# Kyocera_breakout_board.net
KiCad netlist of a schematic drawn in EasyEDA
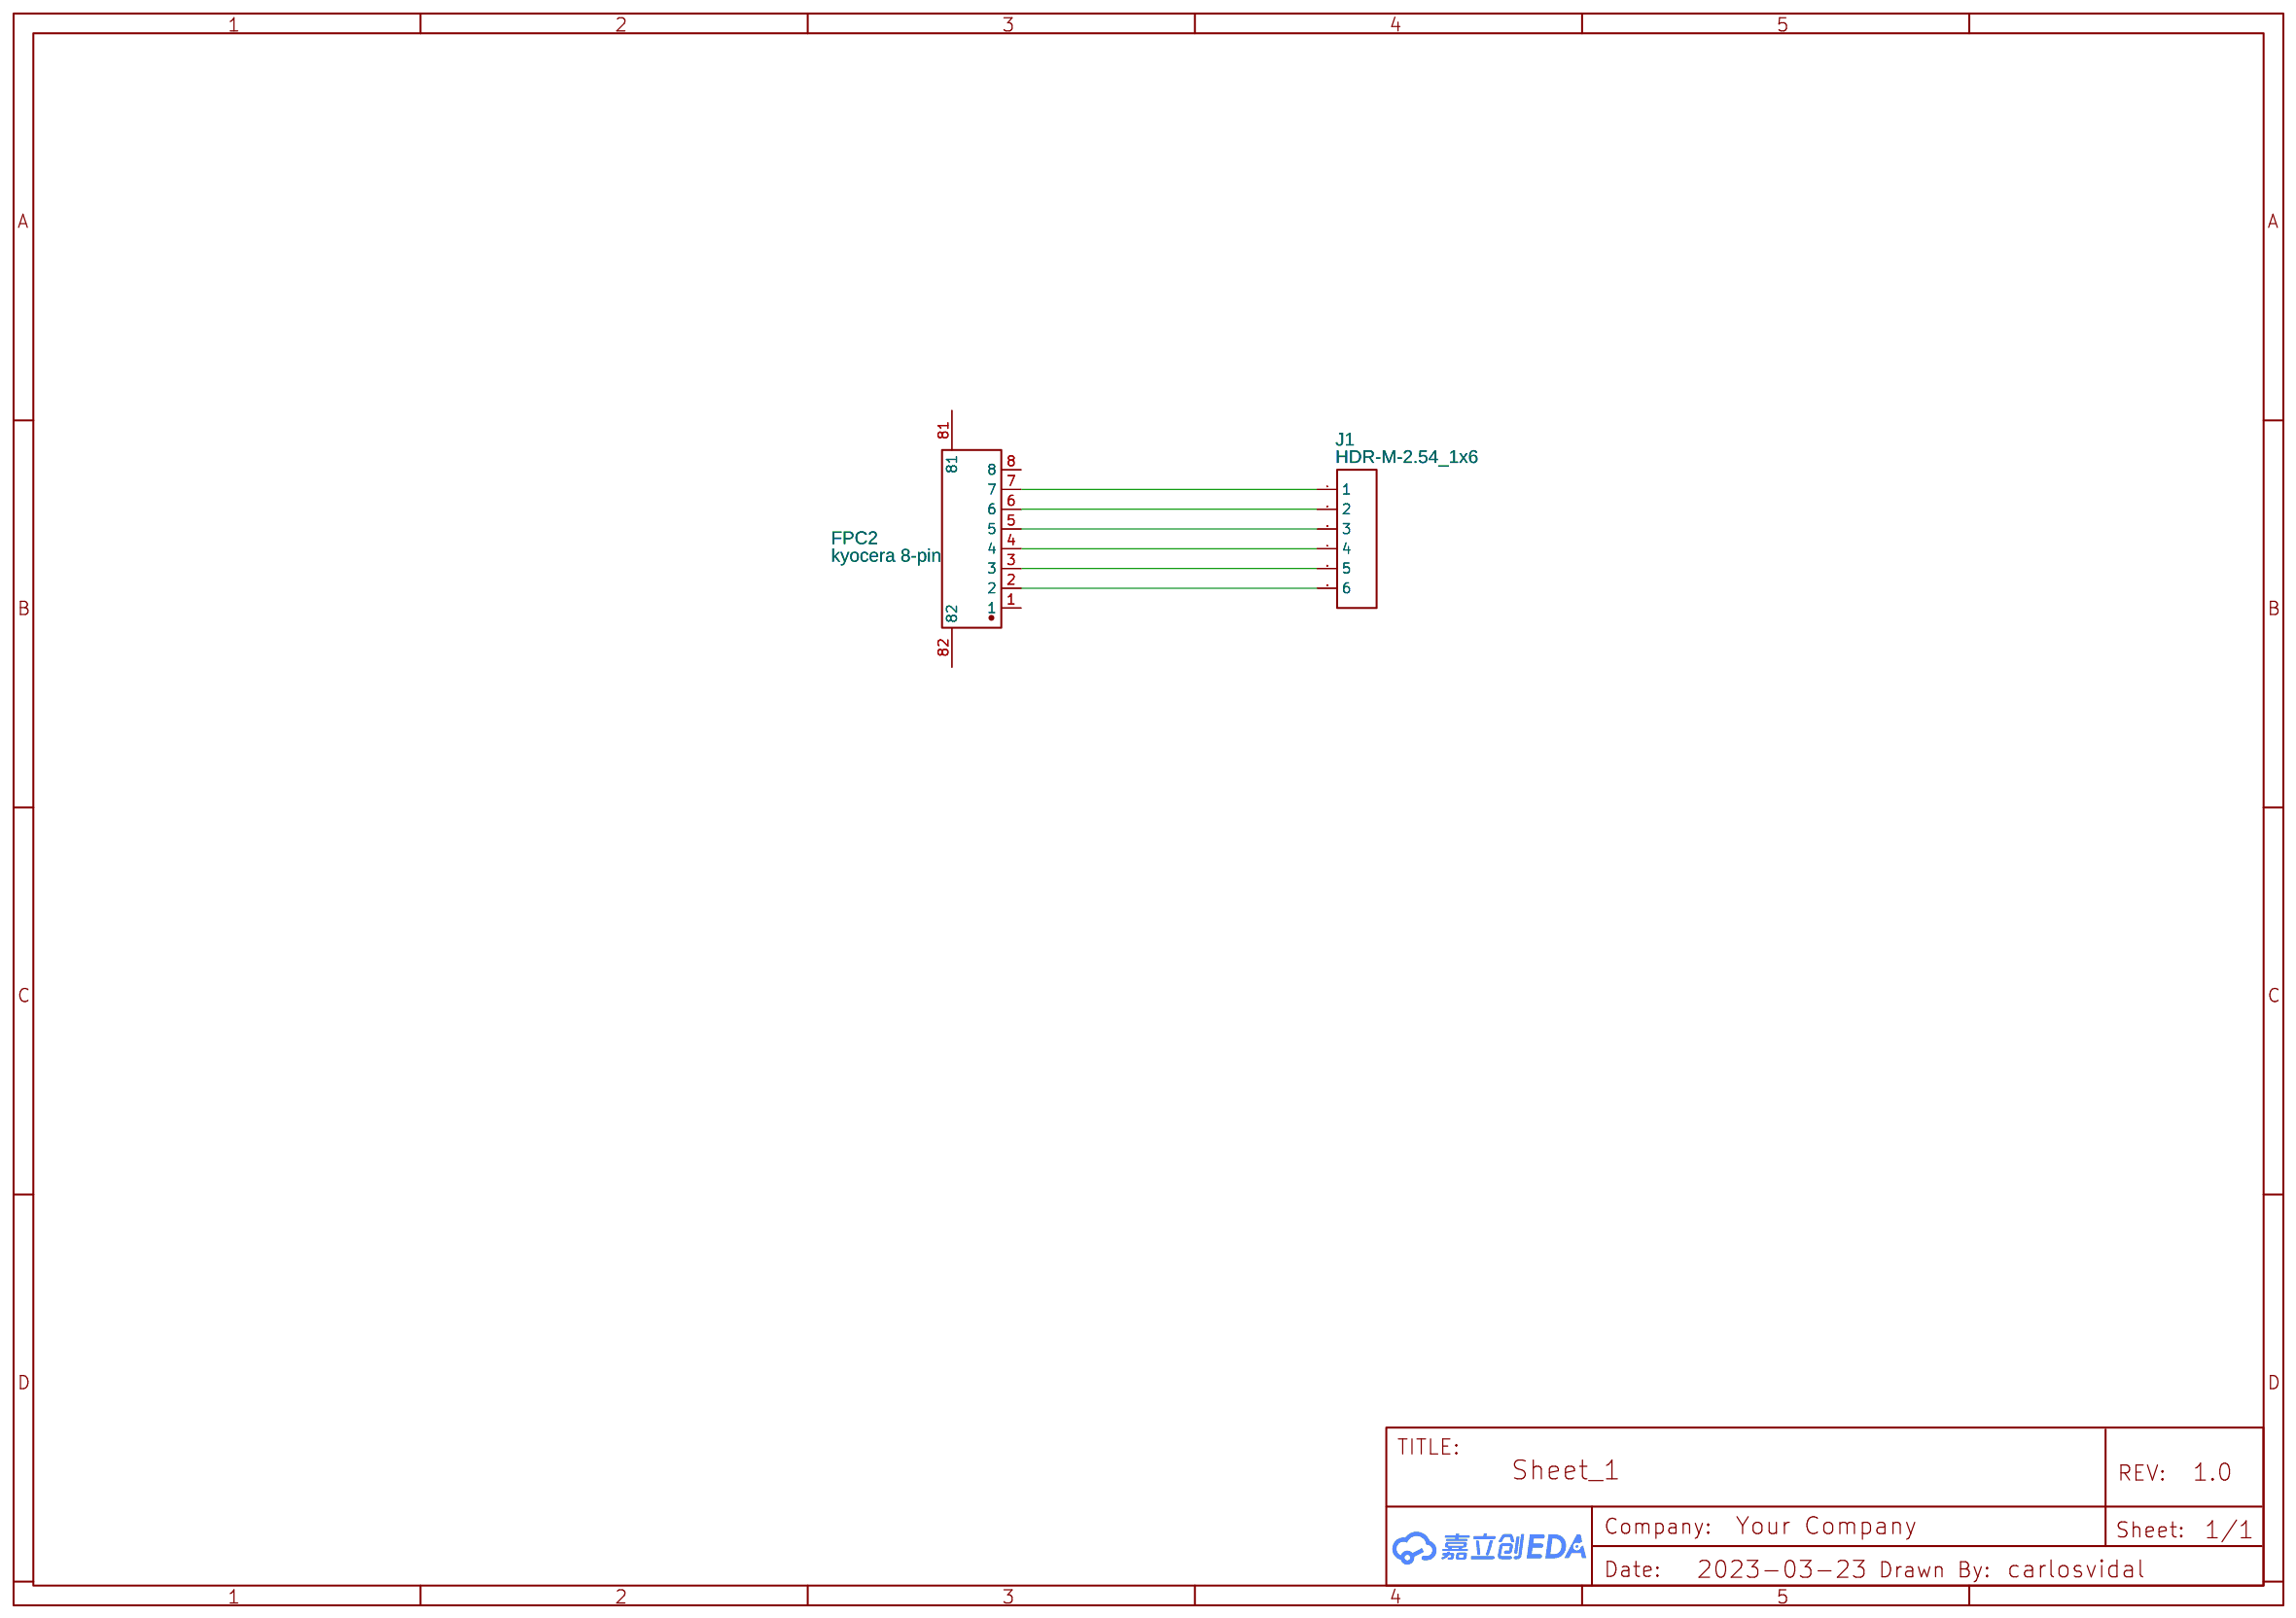
[diagram p0: schematic sheet]

(export (version "E")
  (design (tool "Eeschema 10.0.6"))
  (components
    (comp (ref "FPC2")
      (value "kyocera 8-pin")
      (fields
        (field (name "Manufacturer Part") "046288080000846+")
        (field (name "Manufacturer") "Kyocera AVX")
      )
      (libsource (lib "") (part "kyocera 8-pin"))
    )
    (comp (ref "J1") (value "HDR-M-2.54_1x6") (libsource (lib "") (part "HDR-M-2.54_1x6")))
  )
  (nets
    (net (code "1") (name "Net-(FPC2-Pad2)") (class "Default")
      (node (ref "FPC2") (pin "2") (pinfunction "2_2") (pintype "unspecified"))
      (node (ref "J1") (pin "6") (pinfunction "6_6") (pintype "input"))
    )
    (net (code "2") (name "Net-(FPC2-Pad3)") (class "Default")
      (node (ref "FPC2") (pin "3") (pinfunction "3_3") (pintype "unspecified"))
      (node (ref "J1") (pin "5") (pinfunction "5_5") (pintype "input"))
    )
    (net (code "3") (name "Net-(FPC2-Pad4)") (class "Default")
      (node (ref "FPC2") (pin "4") (pinfunction "4_4") (pintype "unspecified"))
      (node (ref "J1") (pin "4") (pinfunction "4_4") (pintype "input"))
    )
    (net (code "4") (name "Net-(FPC2-Pad5)") (class "Default")
      (node (ref "FPC2") (pin "5") (pinfunction "5_5") (pintype "unspecified"))
      (node (ref "J1") (pin "3") (pinfunction "3_3") (pintype "input"))
    )
    (net (code "5") (name "Net-(FPC2-Pad6)") (class "Default")
      (node (ref "FPC2") (pin "6") (pinfunction "6_6") (pintype "unspecified"))
      (node (ref "J1") (pin "2") (pinfunction "2_2") (pintype "input"))
    )
    (net (code "6") (name "Net-(FPC2-Pad7)") (class "Default")
      (node (ref "FPC2") (pin "7") (pinfunction "7_7") (pintype "unspecified"))
      (node (ref "J1") (pin "1") (pinfunction "1_1") (pintype "input"))
    )
    (net (code "7") (name "unconnected-(FPC2-Pad1)") (class "Default")
      (node (ref "FPC2") (pin "1") (pinfunction "1_1") (pintype "unspecified"))
    )
    (net (code "8") (name "unconnected-(FPC2-Pad8)") (class "Default")
      (node (ref "FPC2") (pin "8") (pinfunction "8_8") (pintype "unspecified"))
    )
    (net (code "9") (name "unconnected-(FPC2-Pad81)") (class "Default")
      (node (ref "FPC2") (pin "81") (pinfunction "81_81") (pintype "unspecified"))
    )
    (net (code "10") (name "unconnected-(FPC2-Pad82)") (class "Default")
      (node (ref "FPC2") (pin "82") (pinfunction "82_82") (pintype "unspecified"))
    )
  )
)
